# MAG.net
KiCad netlist of a schematic drawn in Altium Designer
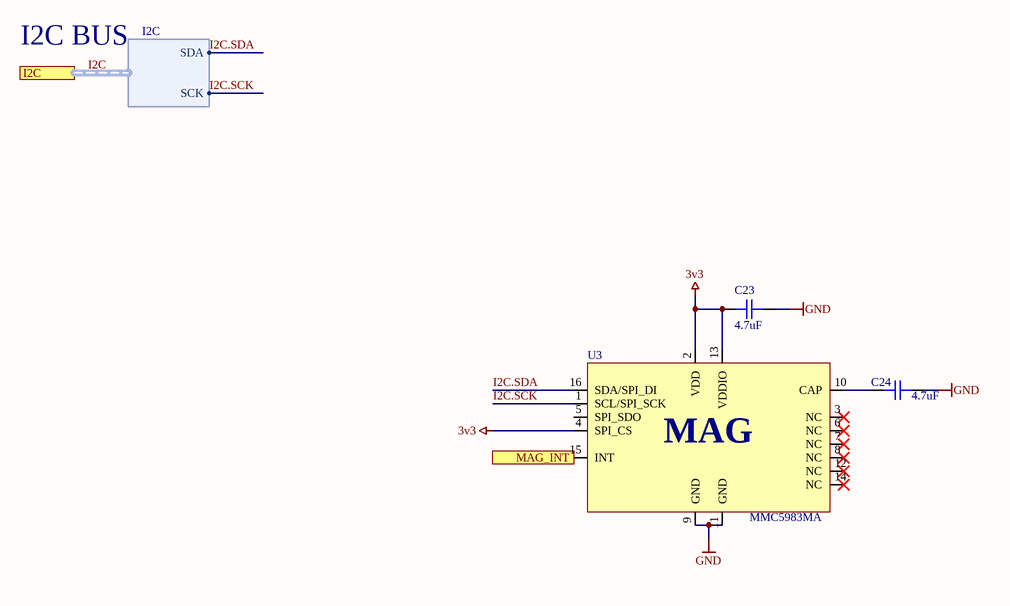
[diagram p0: MAG.SchDoc]

(export (version "E")
  (design (tool "Eeschema 10.0.6"))
  (components
    (comp (ref "C23")
      (value "4.7uF")
      (footprint "CAP_0402")
      (description "Capacitor SMD 0402 10V")
      (fields (field (name "Comment") "C0402_10V"))
      (libsource (lib "Schematic-Lib-PhilsLab") (part "CAP_0402_10V"))
    )
    (comp (ref "C24")
      (value "4.7uF")
      (footprint "CAP_0402")
      (description "Capacitor SMD 0402 10V")
      (fields (field (name "Comment") "C0402_10V"))
      (libsource (lib "Schematic-Lib-PhilsLab") (part "CAP_0402_10V"))
    )
    (comp (ref "U3")
      (value "MMC5983MA")
      (footprint "MMC5983MA-LGA")
      (description "±8 Gauss, High Performance 3-axis Magnetic Sensor I2C/SPI")
      (fields (field (name "MANUFACTURER") "MEMSIC"))
      (libsource (lib "Schematic-Lib-PhilsLab") (part "MMC5983MA"))
    )
  )
  (nets
    (net (code "2") (name "/I2C.SCK") (class "Default")
      (node (ref "U3") (pin "1") (pinfunction "SCL/SPI_SCK_1") (pintype "passive"))
    )
    (net (code "3") (name "/I2C.SDA") (class "Default")
      (node (ref "U3") (pin "16") (pinfunction "SDA/SPI_DI_16") (pintype "passive"))
    )
    (net (code "5") (name "/MAG_INT") (class "Default")
      (node (ref "U3") (pin "15") (pinfunction "INT_15") (pintype "passive"))
    )
    (net (code "6") (name "3v3") (class "Default")
      (node (ref "C23") (pin "2") (pinfunction "2_2") (pintype "passive"))
      (node (ref "U3") (pin "13") (pinfunction "VDDIO_13") (pintype "passive"))
      (node (ref "U3") (pin "2") (pinfunction "VDD_2") (pintype "passive"))
      (node (ref "U3") (pin "4") (pinfunction "SPI_CS_4") (pintype "passive"))
    )
    (net (code "7") (name "GND") (class "Default")
      (node (ref "C23") (pin "1") (pinfunction "1_1") (pintype "passive"))
      (node (ref "C24") (pin "2") (pinfunction "2_2") (pintype "passive"))
      (node (ref "U3") (pin "11") (pinfunction "GND_11") (pintype "passive"))
      (node (ref "U3") (pin "9") (pinfunction "GND_9") (pintype "passive"))
    )
    (net (code "8") (name "Net-(U3-CAP)") (class "Default")
      (node (ref "C24") (pin "1") (pinfunction "1_1") (pintype "passive"))
      (node (ref "U3") (pin "10") (pinfunction "CAP_10") (pintype "passive"))
    )
    (net (code "9") (name "unconnected-(U3-NC-Pad3)") (class "Default")
      (node (ref "U3") (pin "3") (pinfunction "NC_3") (pintype "passive+no_connect"))
    )
    (net (code "10") (name "unconnected-(U3-NC-Pad6)") (class "Default")
      (node (ref "U3") (pin "6") (pinfunction "NC_6") (pintype "passive+no_connect"))
    )
    (net (code "11") (name "unconnected-(U3-NC-Pad7)") (class "Default")
      (node (ref "U3") (pin "7") (pinfunction "NC_7") (pintype "passive+no_connect"))
    )
    (net (code "12") (name "unconnected-(U3-NC-Pad8)") (class "Default")
      (node (ref "U3") (pin "8") (pinfunction "NC_8") (pintype "passive+no_connect"))
    )
    (net (code "13") (name "unconnected-(U3-NC-Pad12)") (class "Default")
      (node (ref "U3") (pin "12") (pinfunction "NC_12") (pintype "passive+no_connect"))
    )
    (net (code "14") (name "unconnected-(U3-NC-Pad14)") (class "Default")
      (node (ref "U3") (pin "14") (pinfunction "NC_14") (pintype "passive+no_connect"))
    )
    (net (code "15") (name "unconnected-(U3-SPI_SDO-Pad5)") (class "Default")
      (node (ref "U3") (pin "5") (pinfunction "SPI_SDO_5") (pintype "passive"))
    )
  )
)
